# piezo-jfet-buffer-simple.net
KiCad netlist of a schematic drawn in EAGLE
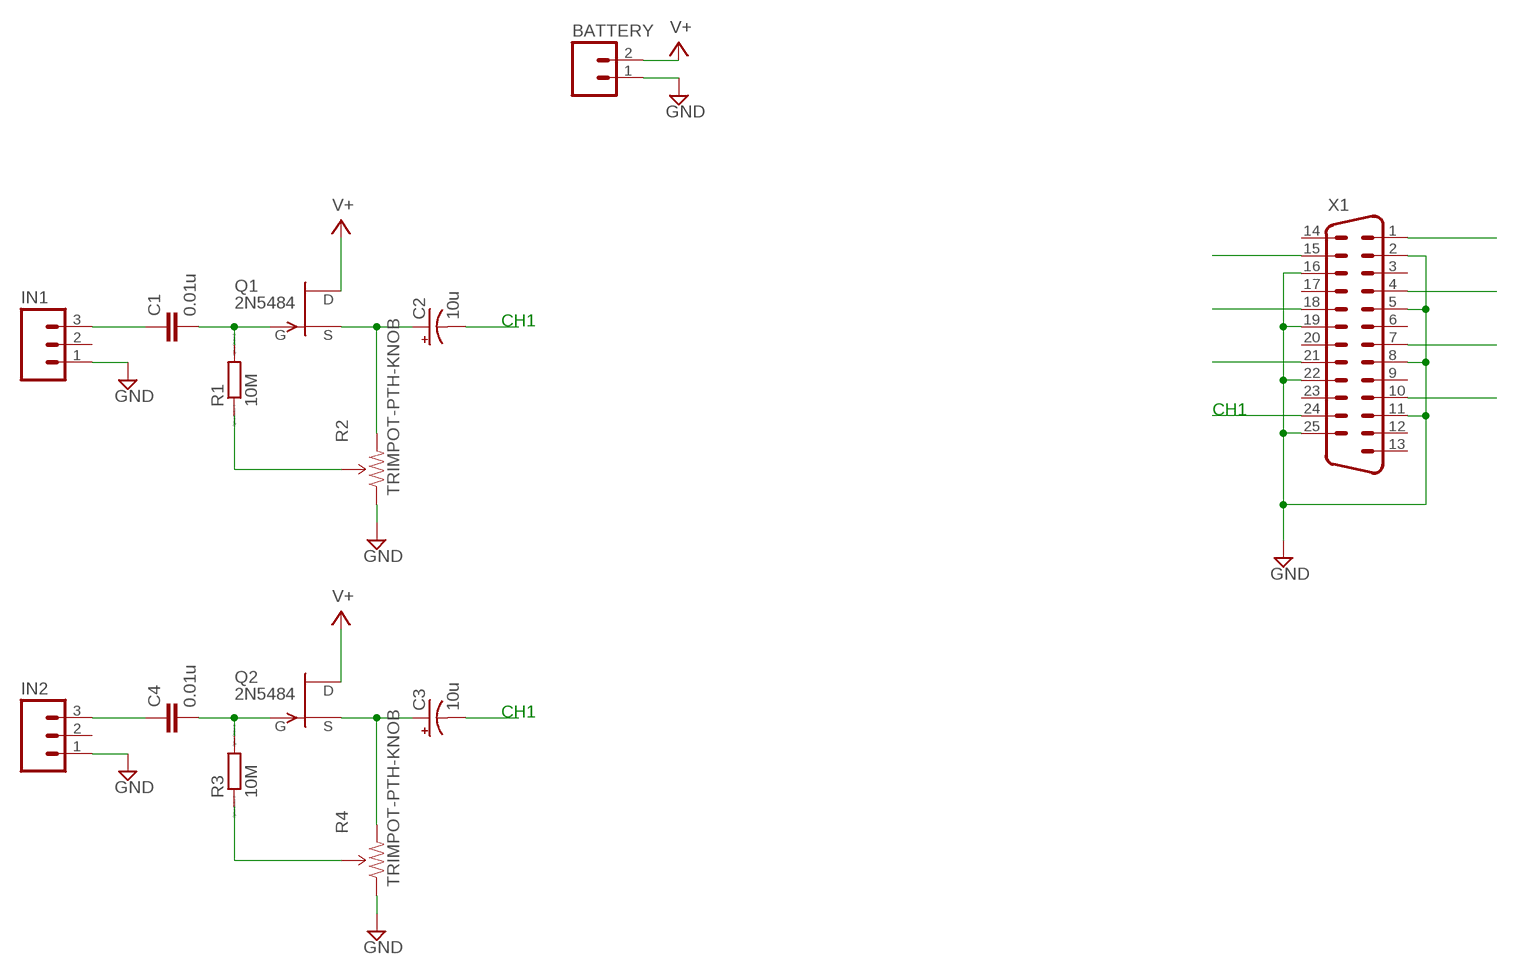
[diagram p0: schematic, sheet 1]

(export (version "E")
  (design (tool "Eeschema 10.0.6"))
  (components
    (comp (ref "BATTERY")
      (value "M02PTH")
      (footprint "eagle-import:1X02")
      (libsource (lib "eagle-import") (part "M02PTH"))
    )
    (comp (ref "C1")
      (value "0.01u")
      (footprint "eagle-import:C5B3")
      (libsource (lib "eagle-import") (part "C5/3"))
    )
    (comp (ref "C2")
      (value "10u")
      (footprint "eagle-import:CPOL-RADIAL-10UF-25V")
      (libsource (lib "eagle-import") (part "CAP_POLPTH2"))
    )
    (comp (ref "C3")
      (value "10u")
      (footprint "eagle-import:CPOL-RADIAL-10UF-25V")
      (libsource (lib "eagle-import") (part "CAP_POLPTH2"))
    )
    (comp (ref "C4")
      (value "0.01u")
      (footprint "eagle-import:C5B3")
      (libsource (lib "eagle-import") (part "C5/3"))
    )
    (comp (ref "IN1")
      (value "M03LOCK")
      (footprint "eagle-import:1X03_LOCK")
      (libsource (lib "eagle-import") (part "M03LOCK"))
    )
    (comp (ref "IN2")
      (value "M03LOCK")
      (footprint "eagle-import:1X03_LOCK")
      (libsource (lib "eagle-import") (part "M03LOCK"))
    )
    (comp (ref "Q1")
      (value "2N5484")
      (footprint "eagle-import:TO92-")
      (libsource (lib "eagle-import") (part "?5482N4"))
    )
    (comp (ref "Q2")
      (value "2N5484")
      (footprint "eagle-import:TO92-")
      (libsource (lib "eagle-import") (part "?5482N4"))
    )
    (comp (ref "R1")
      (value "10M")
      (footprint "eagle-import:0204_7")
      (libsource (lib "eagle-import") (part "R0204/7"))
    )
    (comp (ref "R2")
      (value "TRIMPOT-PTH-KNOB")
      (footprint "eagle-import:3386U")
      (libsource (lib "eagle-import") (part "TRIMPOT-PTH-KNOB"))
    )
    (comp (ref "R3")
      (value "10M")
      (footprint "eagle-import:0204_7")
      (libsource (lib "eagle-import") (part "R0204/7"))
    )
    (comp (ref "R4")
      (value "TRIMPOT-PTH-KNOB")
      (footprint "eagle-import:3386U")
      (libsource (lib "eagle-import") (part "TRIMPOT-PTH-KNOB"))
    )
    (comp (ref "X1")
      (value "DB25H")
      (footprint "eagle-import:M25H")
      (libsource (lib "eagle-import") (part "DB25H"))
    )
  )
  (nets
    (net (code "1") (name "/CH1") (class "Default")
      (node (ref "C2") (pin "2") (pinfunction "-_2") (pintype "passive"))
      (node (ref "X1") (pin "24") (pinfunction "24_24") (pintype "passive"))
    )
    (net (code "2") (name "/CH2") (class "Default")
      (node (ref "C3") (pin "2") (pinfunction "-_2") (pintype "passive"))
      (node (ref "X1") (pin "10") (pinfunction "10_10") (pintype "passive"))
    )
    (net (code "3") (name "GND") (class "Default")
      (node (ref "BATTERY") (pin "1") (pinfunction "1_1") (pintype "passive"))
      (node (ref "IN1") (pin "1") (pinfunction "1_1") (pintype "passive"))
      (node (ref "IN2") (pin "1") (pinfunction "1_1") (pintype "passive"))
      (node (ref "R2") (pin "1") (pinfunction "CCW_1") (pintype "passive"))
      (node (ref "R4") (pin "1") (pinfunction "CCW_1") (pintype "passive"))
      (node (ref "X1") (pin "11") (pinfunction "11_11") (pintype "passive"))
      (node (ref "X1") (pin "16") (pinfunction "16_16") (pintype "passive"))
      (node (ref "X1") (pin "19") (pinfunction "19_19") (pintype "passive"))
      (node (ref "X1") (pin "2") (pinfunction "2_2") (pintype "passive"))
      (node (ref "X1") (pin "22") (pinfunction "22_22") (pintype "passive"))
      (node (ref "X1") (pin "25") (pinfunction "25_25") (pintype "passive"))
      (node (ref "X1") (pin "5") (pinfunction "5_5") (pintype "passive"))
      (node (ref "X1") (pin "8") (pinfunction "8_8") (pintype "passive"))
    )
    (net (code "4") (name "Net-(C1-Pad1)") (class "Default")
      (node (ref "C1") (pin "1") (pinfunction "1_1") (pintype "passive"))
      (node (ref "IN1") (pin "3") (pinfunction "3_3") (pintype "passive"))
    )
    (net (code "5") (name "Net-(C2-+)") (class "Default")
      (node (ref "C2") (pin "1") (pinfunction "+_1") (pintype "passive"))
      (node (ref "Q1") (pin "2") (pinfunction "S_2") (pintype "passive"))
      (node (ref "R2") (pin "3") (pinfunction "CW_3") (pintype "passive"))
    )
    (net (code "6") (name "Net-(C3-+)") (class "Default")
      (node (ref "C3") (pin "1") (pinfunction "+_1") (pintype "passive"))
      (node (ref "Q2") (pin "2") (pinfunction "S_2") (pintype "passive"))
      (node (ref "R4") (pin "3") (pinfunction "CW_3") (pintype "passive"))
    )
    (net (code "7") (name "Net-(C4-Pad1)") (class "Default")
      (node (ref "C4") (pin "1") (pinfunction "1_1") (pintype "passive"))
      (node (ref "IN2") (pin "3") (pinfunction "3_3") (pintype "passive"))
    )
    (net (code "8") (name "Net-(Q1-G)") (class "Default")
      (node (ref "C1") (pin "2") (pinfunction "2_2") (pintype "passive"))
      (node (ref "Q1") (pin "1") (pinfunction "G_1") (pintype "passive"))
      (node (ref "R1") (pin "2") (pinfunction "2_2") (pintype "passive"))
    )
    (net (code "9") (name "Net-(Q2-G)") (class "Default")
      (node (ref "C4") (pin "2") (pinfunction "2_2") (pintype "passive"))
      (node (ref "Q2") (pin "1") (pinfunction "G_1") (pintype "passive"))
      (node (ref "R3") (pin "2") (pinfunction "2_2") (pintype "passive"))
    )
    (net (code "10") (name "Net-(R2-WIPER)") (class "Default")
      (node (ref "R1") (pin "1") (pinfunction "1_1") (pintype "passive"))
      (node (ref "R2") (pin "2") (pinfunction "WIPER_2") (pintype "passive"))
    )
    (net (code "11") (name "Net-(R4-WIPER)") (class "Default")
      (node (ref "R3") (pin "1") (pinfunction "1_1") (pintype "passive"))
      (node (ref "R4") (pin "2") (pinfunction "WIPER_2") (pintype "passive"))
    )
    (net (code "12") (name "V+") (class "Default")
      (node (ref "BATTERY") (pin "2") (pinfunction "2_2") (pintype "passive"))
      (node (ref "Q1") (pin "3") (pinfunction "D_3") (pintype "passive"))
      (node (ref "Q2") (pin "3") (pinfunction "D_3") (pintype "passive"))
    )
    (net (code "13") (name "unconnected-(IN1-Pad2)") (class "Default")
      (node (ref "IN1") (pin "2") (pinfunction "2_2") (pintype "passive"))
    )
    (net (code "14") (name "unconnected-(IN2-Pad2)") (class "Default")
      (node (ref "IN2") (pin "2") (pinfunction "2_2") (pintype "passive"))
    )
    (net (code "15") (name "unconnected-(X1-Pad1)") (class "Default")
      (node (ref "X1") (pin "1") (pinfunction "1_1") (pintype "passive"))
    )
    (net (code "16") (name "unconnected-(X1-Pad3)") (class "Default")
      (node (ref "X1") (pin "3") (pinfunction "3_3") (pintype "passive"))
    )
    (net (code "17") (name "unconnected-(X1-Pad4)") (class "Default")
      (node (ref "X1") (pin "4") (pinfunction "4_4") (pintype "passive"))
    )
    (net (code "18") (name "unconnected-(X1-Pad6)") (class "Default")
      (node (ref "X1") (pin "6") (pinfunction "6_6") (pintype "passive"))
    )
    (net (code "19") (name "unconnected-(X1-Pad7)") (class "Default")
      (node (ref "X1") (pin "7") (pinfunction "7_7") (pintype "passive"))
    )
    (net (code "20") (name "unconnected-(X1-Pad9)") (class "Default")
      (node (ref "X1") (pin "9") (pinfunction "9_9") (pintype "passive"))
    )
    (net (code "21") (name "unconnected-(X1-Pad12)") (class "Default")
      (node (ref "X1") (pin "12") (pinfunction "12_12") (pintype "passive"))
    )
    (net (code "22") (name "unconnected-(X1-Pad13)") (class "Default")
      (node (ref "X1") (pin "13") (pinfunction "13_13") (pintype "passive"))
    )
    (net (code "23") (name "unconnected-(X1-Pad14)") (class "Default")
      (node (ref "X1") (pin "14") (pinfunction "14_14") (pintype "passive"))
    )
    (net (code "24") (name "unconnected-(X1-Pad15)") (class "Default")
      (node (ref "X1") (pin "15") (pinfunction "15_15") (pintype "passive"))
    )
    (net (code "25") (name "unconnected-(X1-Pad17)") (class "Default")
      (node (ref "X1") (pin "17") (pinfunction "17_17") (pintype "passive"))
    )
    (net (code "26") (name "unconnected-(X1-Pad18)") (class "Default")
      (node (ref "X1") (pin "18") (pinfunction "18_18") (pintype "passive"))
    )
    (net (code "27") (name "unconnected-(X1-Pad20)") (class "Default")
      (node (ref "X1") (pin "20") (pinfunction "20_20") (pintype "passive"))
    )
    (net (code "28") (name "unconnected-(X1-Pad21)") (class "Default")
      (node (ref "X1") (pin "21") (pinfunction "21_21") (pintype "passive"))
    )
    (net (code "29") (name "unconnected-(X1-Pad23)") (class "Default")
      (node (ref "X1") (pin "23") (pinfunction "23_23") (pintype "passive"))
    )
  )
)
